# adapter.net
KiCad netlist of a schematic drawn in EAGLE
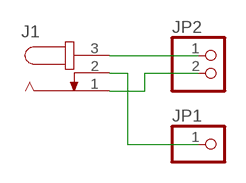
[diagram p0: schematic, sheet 1]

(export (version "E")
  (design (tool "Eeschema 10.0.6"))
  (components
    (comp (ref "J1")
      (value "JACK-PLUG0")
      (footprint "eagle-import:SPC4077")
      (libsource (lib "eagle-import") (part "JACK-PLUG0"))
    )
    (comp (ref "JP1")
      (value "PINHD-1X1")
      (footprint "eagle-import:1X01")
      (libsource (lib "eagle-import") (part "PINHD-1X1"))
    )
    (comp (ref "JP2")
      (value "PINHD-1X2")
      (footprint "eagle-import:1X02")
      (libsource (lib "eagle-import") (part "PINHD-1X2"))
    )
  )
  (nets
    (net (code "1") (name "Net-(J1-Pad1)") (class "Default")
      (node (ref "J1") (pin "1") (pinfunction "1_1") (pintype "passive"))
      (node (ref "JP2") (pin "2") (pinfunction "2_2") (pintype "passive"))
    )
    (net (code "2") (name "Net-(J1-Pad2)") (class "Default")
      (node (ref "J1") (pin "2") (pinfunction "2_2") (pintype "passive"))
      (node (ref "JP1") (pin "1") (pinfunction "1_1") (pintype "passive"))
    )
    (net (code "3") (name "Net-(J1-Pad3)") (class "Default")
      (node (ref "J1") (pin "3") (pinfunction "3_3") (pintype "passive"))
      (node (ref "JP2") (pin "1") (pinfunction "1_1") (pintype "passive"))
    )
  )
)
